# MAGI_sBatteryPower.net
KiCad netlist of a schematic drawn in Altium Designer
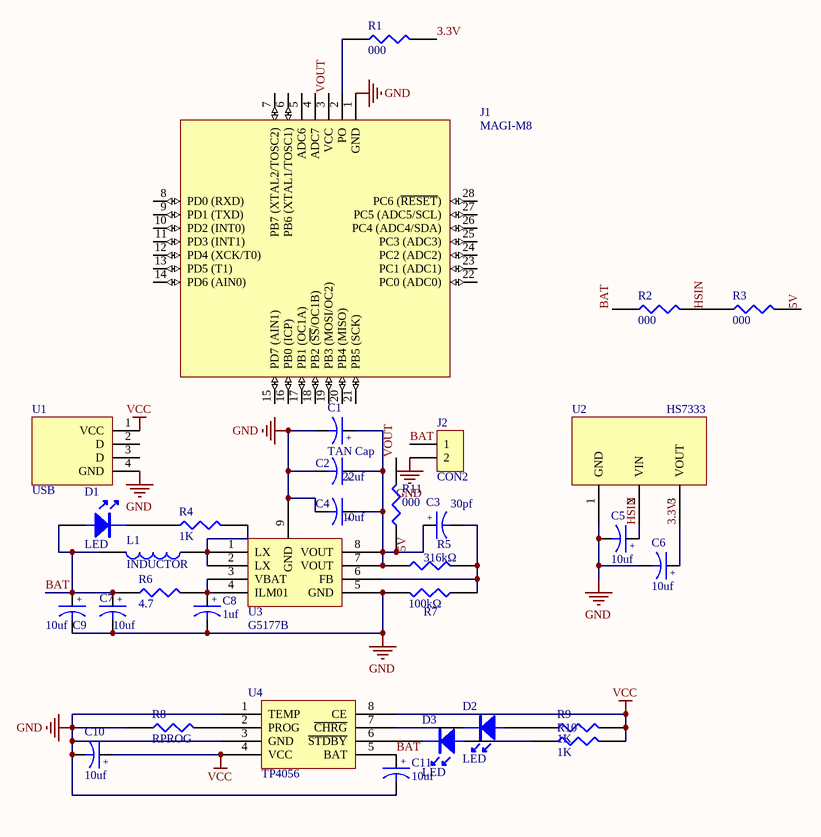
[diagram p0: MAGI'sBatteryPower.SchDoc]

(export (version "E")
  (design (tool "Eeschema 10.0.6"))
  (components
    (comp (ref "C1")
      (value "TAN Cap")
      (footprint "TAN-D-7343")
      (description "Capacitor")
      (libsource (lib "电容器") (part "CAPACITOR POL"))
    )
    (comp (ref "C2")
      (value "22uf")
      (footprint "14-1210")
      (description "Capacitor")
      (libsource (lib "电容器") (part "CAPACITOR POL"))
    )
    (comp (ref "C3")
      (value "30pf")
      (footprint "6-0805_N")
      (description "Capacitor")
      (libsource (lib "电容器") (part "CAPACITOR POL"))
    )
    (comp (ref "C4")
      (value "10uf")
      (footprint "6-0805_N")
      (description "Capacitor")
      (libsource (lib "电容器") (part "CAPACITOR POL"))
    )
    (comp (ref "C5")
      (value "10uf")
      (footprint "6-0805_N")
      (description "Capacitor")
      (libsource (lib "电容器") (part "CAPACITOR POL"))
    )
    (comp (ref "C6")
      (value "10uf")
      (footprint "6-0805_N")
      (description "Capacitor")
      (libsource (lib "电容器") (part "CAPACITOR POL"))
    )
    (comp (ref "C7")
      (value "10uf")
      (footprint "6-0805_N")
      (description "Capacitor")
      (libsource (lib "电容器") (part "CAPACITOR POL"))
    )
    (comp (ref "C8")
      (value "1uf")
      (footprint "6-0805_N")
      (description "Capacitor")
      (libsource (lib "电容器") (part "CAPACITOR POL"))
    )
    (comp (ref "C9")
      (value "10uf")
      (footprint "6-0805_N")
      (description "Capacitor")
      (libsource (lib "电容器") (part "CAPACITOR POL"))
    )
    (comp (ref "C10")
      (value "10uf")
      (footprint "6-0805_N")
      (description "Capacitor")
      (libsource (lib "电容器") (part "CAPACITOR POL"))
    )
    (comp (ref "C11")
      (value "10uf")
      (footprint "6-0805_N")
      (description "Capacitor")
      (libsource (lib "电容器") (part "CAPACITOR POL"))
    )
    (comp (ref "D1") (value "LED") (footprint "6-0805_N") (libsource (lib "二极管") (part "LED")))
    (comp (ref "D2") (value "LED") (footprint "6-0805_N") (libsource (lib "二极管") (part "LED")))
    (comp (ref "D3") (value "LED") (footprint "6-0805_N") (libsource (lib "二极管") (part "LED")))
    (comp (ref "J1") (value "MAGI-M8") (footprint "MAGI-M8") (libsource (lib "MAGI-M8") (part "MAGI-M8")))
    (comp (ref "J2")
      (value "CON2")
      (footprint "CON2")
      (description "Connector")
      (libsource (lib "CON系列") (part "CON2"))
    )
    (comp (ref "L1") (value "INDUCTOR") (footprint "7*7") (libsource (lib "汇总") (part "INDUCTOR")))
    (comp (ref "R1") (value "000") (footprint "6-0805_n") (libsource (lib "电阻器") (part "RES1")))
    (comp (ref "R2") (value "000") (footprint "1608[0603]") (libsource (lib "电阻器") (part "RES1")))
    (comp (ref "R3") (value "000") (footprint "1608[0603]") (libsource (lib "电阻器") (part "RES1")))
    (comp (ref "R4") (value "1K") (footprint "6-0805_N") (libsource (lib "电阻器") (part "RES1")))
    (comp (ref "R5") (value "316kΩ") (footprint "6-0805_N") (libsource (lib "电阻器") (part "RES1")))
    (comp (ref "R6") (value "4.7") (footprint "6-0805_N") (libsource (lib "电阻器") (part "RES1")))
    (comp (ref "R7") (value "100kΩ") (footprint "6-0805_N") (libsource (lib "电阻器") (part "RES1")))
    (comp (ref "R8") (value "RPROG") (footprint "6-0805_N") (libsource (lib "电阻器") (part "RES1")))
    (comp (ref "R9") (value "1K") (footprint "6-0805_N") (libsource (lib "电阻器") (part "RES1")))
    (comp (ref "R10") (value "1K") (footprint "6-0805_N") (libsource (lib "电阻器") (part "RES1")))
    (comp (ref "R11") (value "000") (footprint "6-0805_N") (libsource (lib "电阻器") (part "RES1")))
    (comp (ref "U1") (value "USB") (footprint "MicroUSB") (libsource (lib "USB接口") (part "USB")))
    (comp (ref "U2") (value "HS7333") (footprint "HS7333") (libsource (lib "PMIC") (part "HS7333")))
    (comp (ref "U3") (value "G5177B") (footprint "G5177B") (libsource (lib "PMIC") (part "G5177B")))
    (comp (ref "U4") (value "TP4056") (footprint "TP4056") (libsource (lib "PMIC") (part "TP4056")))
  )
  (nets
    (net (code "1") (name "/3.3V") (class "Default")
      (node (ref "C6") (pin "1") (pinfunction "1_1") (pintype "passive"))
      (node (ref "R1") (pin "2") (pinfunction "2_2") (pintype "passive"))
      (node (ref "U2") (pin "3") (pinfunction "VOUT_3") (pintype "passive"))
    )
    (net (code "2") (name "/5V") (class "Default")
      (node (ref "C1") (pin "1") (pinfunction "1_1") (pintype "passive"))
      (node (ref "C2") (pin "1") (pinfunction "1_1") (pintype "passive"))
      (node (ref "C3") (pin "1") (pinfunction "1_1") (pintype "passive"))
      (node (ref "C4") (pin "1") (pinfunction "1_1") (pintype "passive"))
      (node (ref "R11") (pin "1") (pinfunction "1_1") (pintype "passive"))
      (node (ref "R3") (pin "2") (pinfunction "2_2") (pintype "passive"))
      (node (ref "R5") (pin "1") (pinfunction "1_1") (pintype "passive"))
      (node (ref "U3") (pin "7") (pinfunction "VOUT_7") (pintype "passive"))
      (node (ref "U3") (pin "8") (pinfunction "VOUT_8") (pintype "passive"))
    )
    (net (code "3") (name "/BAT") (class "Default")
      (node (ref "C11") (pin "1") (pinfunction "1_1") (pintype "passive"))
      (node (ref "C7") (pin "1") (pinfunction "1_1") (pintype "passive"))
      (node (ref "C9") (pin "1") (pinfunction "1_1") (pintype "passive"))
      (node (ref "D1") (pin "1") (pinfunction "1_1") (pintype "passive"))
      (node (ref "J2") (pin "1") (pinfunction "1_1") (pintype "passive"))
      (node (ref "L1") (pin "2") (pinfunction "2_2") (pintype "passive"))
      (node (ref "R2") (pin "1") (pinfunction "1_1") (pintype "passive"))
      (node (ref "R6") (pin "1") (pinfunction "1_1") (pintype "passive"))
      (node (ref "U4") (pin "5") (pinfunction "BAT_5") (pintype "passive"))
    )
    (net (code "4") (name "/HSIN") (class "Default")
      (node (ref "C5") (pin "1") (pinfunction "1_1") (pintype "passive"))
      (node (ref "R2") (pin "2") (pinfunction "2_2") (pintype "passive"))
      (node (ref "R3") (pin "1") (pinfunction "1_1") (pintype "passive"))
      (node (ref "U2") (pin "2") (pinfunction "VIN_2") (pintype "passive"))
    )
    (net (code "5") (name "/VOUT") (class "Default")
      (node (ref "J1") (pin "3") (pinfunction "VCC_3") (pintype "power_in"))
      (node (ref "R11") (pin "2") (pinfunction "2_2") (pintype "passive"))
    )
    (net (code "6") (name "GND") (class "Default")
      (node (ref "C1") (pin "2") (pinfunction "2_2") (pintype "passive"))
      (node (ref "C10") (pin "2") (pinfunction "2_2") (pintype "passive"))
      (node (ref "C11") (pin "2") (pinfunction "2_2") (pintype "passive"))
      (node (ref "C2") (pin "2") (pinfunction "2_2") (pintype "passive"))
      (node (ref "C4") (pin "2") (pinfunction "2_2") (pintype "passive"))
      (node (ref "C5") (pin "2") (pinfunction "2_2") (pintype "passive"))
      (node (ref "C6") (pin "2") (pinfunction "2_2") (pintype "passive"))
      (node (ref "C7") (pin "2") (pinfunction "2_2") (pintype "passive"))
      (node (ref "C8") (pin "2") (pinfunction "2_2") (pintype "passive"))
      (node (ref "C9") (pin "2") (pinfunction "2_2") (pintype "passive"))
      (node (ref "J1") (pin "1") (pinfunction "GND_1") (pintype "power_in"))
      (node (ref "J2") (pin "2") (pinfunction "2_2") (pintype "passive"))
      (node (ref "R7") (pin "2") (pinfunction "2_2") (pintype "passive"))
      (node (ref "R8") (pin "1") (pinfunction "1_1") (pintype "passive"))
      (node (ref "U1") (pin "4") (pinfunction "GND_4") (pintype "passive"))
      (node (ref "U2") (pin "1") (pinfunction "GND_1") (pintype "passive"))
      (node (ref "U3") (pin "5") (pinfunction "GND_5") (pintype "passive"))
      (node (ref "U3") (pin "9") (pinfunction "GND_9") (pintype "passive"))
      (node (ref "U4") (pin "1") (pinfunction "TEMP_1") (pintype "passive"))
      (node (ref "U4") (pin "3") (pinfunction "GND_3") (pintype "passive"))
    )
    (net (code "7") (name "Net-(D1-Pad2)") (class "Default")
      (node (ref "D1") (pin "2") (pinfunction "2_2") (pintype "passive"))
      (node (ref "R4") (pin "1") (pinfunction "1_1") (pintype "passive"))
    )
    (net (code "8") (name "Net-(D2-Pad1)") (class "Default")
      (node (ref "D2") (pin "1") (pinfunction "1_1") (pintype "passive"))
      (node (ref "R9") (pin "1") (pinfunction "1_1") (pintype "passive"))
    )
    (net (code "9") (name "Net-(D3-Pad1)") (class "Default")
      (node (ref "D3") (pin "1") (pinfunction "1_1") (pintype "passive"))
      (node (ref "R10") (pin "1") (pinfunction "1_1") (pintype "passive"))
    )
    (net (code "10") (name "Net-(J1-PO)") (class "Default")
      (node (ref "J1") (pin "2") (pinfunction "PO_2") (pintype "power_in"))
      (node (ref "R1") (pin "1") (pinfunction "1_1") (pintype "passive"))
    )
    (net (code "11") (name "Net-(L1-Pad1)") (class "Default")
      (node (ref "L1") (pin "1") (pinfunction "1_1") (pintype "passive"))
      (node (ref "R4") (pin "2") (pinfunction "2_2") (pintype "passive"))
      (node (ref "U3") (pin "1") (pinfunction "LX_1") (pintype "passive"))
      (node (ref "U3") (pin "2") (pinfunction "LX_2") (pintype "passive"))
    )
    (net (code "12") (name "Net-(U3-FB)") (class "Default")
      (node (ref "C3") (pin "2") (pinfunction "2_2") (pintype "passive"))
      (node (ref "R5") (pin "2") (pinfunction "2_2") (pintype "passive"))
      (node (ref "R7") (pin "1") (pinfunction "1_1") (pintype "passive"))
      (node (ref "U3") (pin "6") (pinfunction "FB_6") (pintype "passive"))
    )
    (net (code "13") (name "Net-(U3-ILM01)") (class "Default")
      (node (ref "C8") (pin "1") (pinfunction "1_1") (pintype "passive"))
      (node (ref "R6") (pin "2") (pinfunction "2_2") (pintype "passive"))
      (node (ref "U3") (pin "3") (pinfunction "VBAT_3") (pintype "passive"))
      (node (ref "U3") (pin "4") (pinfunction "ILM01_4") (pintype "passive"))
    )
    (net (code "14") (name "Net-(U4-PROG)") (class "Default")
      (node (ref "R8") (pin "2") (pinfunction "2_2") (pintype "passive"))
      (node (ref "U4") (pin "2") (pinfunction "PROG_2") (pintype "passive"))
    )
    (net (code "15") (name "Net-(U4-~{CHRG})") (class "Default")
      (node (ref "D2") (pin "2") (pinfunction "2_2") (pintype "passive"))
      (node (ref "U4") (pin "7") (pinfunction "~{CHRG}_7") (pintype "passive"))
    )
    (net (code "16") (name "Net-(U4-~{STDBY})") (class "Default")
      (node (ref "D3") (pin "2") (pinfunction "2_2") (pintype "passive"))
      (node (ref "U4") (pin "6") (pinfunction "~{STDBY}_6") (pintype "passive"))
    )
    (net (code "17") (name "VCC") (class "Default")
      (node (ref "C10") (pin "1") (pinfunction "1_1") (pintype "passive"))
      (node (ref "R10") (pin "2") (pinfunction "2_2") (pintype "passive"))
      (node (ref "R9") (pin "2") (pinfunction "2_2") (pintype "passive"))
      (node (ref "U1") (pin "1") (pinfunction "VCC_1") (pintype "passive"))
      (node (ref "U4") (pin "4") (pinfunction "VCC_4") (pintype "passive"))
      (node (ref "U4") (pin "8") (pinfunction "CE_8") (pintype "passive"))
    )
    (net (code "18") (name "unconnected-(J1-ADC6-Pad5)") (class "Default")
      (node (ref "J1") (pin "5") (pinfunction "ADC6_5") (pintype "passive"))
    )
    (net (code "19") (name "unconnected-(J1-ADC7-Pad4)") (class "Default")
      (node (ref "J1") (pin "4") (pinfunction "ADC7_4") (pintype "passive"))
    )
    (net (code "20") (name "unconnected-(J1-PB0_(ICP)-Pad16)") (class "Default")
      (node (ref "J1") (pin "16") (pinfunction "PB0_(ICP)_16") (pintype "bidirectional"))
    )
    (net (code "21") (name "unconnected-(J1-PB1_(OC1A)-Pad17)") (class "Default")
      (node (ref "J1") (pin "17") (pinfunction "PB1_(OC1A)_17") (pintype "bidirectional"))
    )
    (net (code "22") (name "unconnected-(J1-PB2_(~{SS}{slash}OC1B)-Pad18)") (class "Default")
      (node (ref "J1") (pin "18") (pinfunction "PB2_(~{SS}/OC1B)_18") (pintype "bidirectional"))
    )
    (net (code "23") (name "unconnected-(J1-PB3_(MOSI{slash}OC2)-Pad19)") (class "Default")
      (node (ref "J1") (pin "19") (pinfunction "PB3_(MOSI/OC2)_19") (pintype "bidirectional"))
    )
    (net (code "24") (name "unconnected-(J1-PB4_(MISO)-Pad20)") (class "Default")
      (node (ref "J1") (pin "20") (pinfunction "PB4_(MISO)_20") (pintype "bidirectional"))
    )
    (net (code "25") (name "unconnected-(J1-PB5_(SCK)-Pad21)") (class "Default")
      (node (ref "J1") (pin "21") (pinfunction "PB5_(SCK)_21") (pintype "bidirectional"))
    )
    (net (code "26") (name "unconnected-(J1-PB6_(XTAL1{slash}TOSC1)-Pad6)") (class "Default")
      (node (ref "J1") (pin "6") (pinfunction "PB6_(XTAL1/TOSC1)_6") (pintype "bidirectional"))
    )
    (net (code "27") (name "unconnected-(J1-PB7_(XTAL2{slash}TOSC2)-Pad7)") (class "Default")
      (node (ref "J1") (pin "7") (pinfunction "PB7_(XTAL2/TOSC2)_7") (pintype "bidirectional"))
    )
    (net (code "28") (name "unconnected-(J1-PC0_(ADC0)-Pad22)") (class "Default")
      (node (ref "J1") (pin "22") (pinfunction "PC0_(ADC0)_22") (pintype "bidirectional"))
    )
    (net (code "29") (name "unconnected-(J1-PC1_(ADC1)-Pad23)") (class "Default")
      (node (ref "J1") (pin "23") (pinfunction "PC1_(ADC1)_23") (pintype "bidirectional"))
    )
    (net (code "30") (name "unconnected-(J1-PC2_(ADC2)-Pad24)") (class "Default")
      (node (ref "J1") (pin "24") (pinfunction "PC2_(ADC2)_24") (pintype "bidirectional"))
    )
    (net (code "31") (name "unconnected-(J1-PC3_(ADC3)-Pad25)") (class "Default")
      (node (ref "J1") (pin "25") (pinfunction "PC3_(ADC3)_25") (pintype "bidirectional"))
    )
    (net (code "32") (name "unconnected-(J1-PC4_(ADC4{slash}SDA)-Pad26)") (class "Default")
      (node (ref "J1") (pin "26") (pinfunction "PC4_(ADC4/SDA)_26") (pintype "bidirectional"))
    )
    (net (code "33") (name "unconnected-(J1-PC5_(ADC5{slash}SCL)-Pad27)") (class "Default")
      (node (ref "J1") (pin "27") (pinfunction "PC5_(ADC5/SCL)_27") (pintype "bidirectional"))
    )
    (net (code "34") (name "unconnected-(J1-PC6_(~{RESET})-Pad28)") (class "Default")
      (node (ref "J1") (pin "28") (pinfunction "PC6_(~{RESET})_28") (pintype "bidirectional"))
    )
    (net (code "35") (name "unconnected-(J1-PD0_(RXD)-Pad8)") (class "Default")
      (node (ref "J1") (pin "8") (pinfunction "PD0_(RXD)_8") (pintype "bidirectional"))
    )
    (net (code "36") (name "unconnected-(J1-PD1_(TXD)-Pad9)") (class "Default")
      (node (ref "J1") (pin "9") (pinfunction "PD1_(TXD)_9") (pintype "bidirectional"))
    )
    (net (code "37") (name "unconnected-(J1-PD2_(INT0)-Pad10)") (class "Default")
      (node (ref "J1") (pin "10") (pinfunction "PD2_(INT0)_10") (pintype "bidirectional"))
    )
    (net (code "38") (name "unconnected-(J1-PD3_(INT1)-Pad11)") (class "Default")
      (node (ref "J1") (pin "11") (pinfunction "PD3_(INT1)_11") (pintype "bidirectional"))
    )
    (net (code "39") (name "unconnected-(J1-PD4_(XCK{slash}T0)-Pad12)") (class "Default")
      (node (ref "J1") (pin "12") (pinfunction "PD4_(XCK/T0)_12") (pintype "bidirectional"))
    )
    (net (code "40") (name "unconnected-(J1-PD5_(T1)-Pad13)") (class "Default")
      (node (ref "J1") (pin "13") (pinfunction "PD5_(T1)_13") (pintype "bidirectional"))
    )
    (net (code "41") (name "unconnected-(J1-PD6_(AIN0)-Pad14)") (class "Default")
      (node (ref "J1") (pin "14") (pinfunction "PD6_(AIN0)_14") (pintype "bidirectional"))
    )
    (net (code "42") (name "unconnected-(J1-PD7_(AIN1)-Pad15)") (class "Default")
      (node (ref "J1") (pin "15") (pinfunction "PD7_(AIN1)_15") (pintype "bidirectional"))
    )
    (net (code "43") (name "unconnected-(U1-D-Pad2)") (class "Default")
      (node (ref "U1") (pin "2") (pinfunction "D_2") (pintype "passive"))
    )
    (net (code "44") (name "unconnected-(U1-D-Pad3)") (class "Default")
      (node (ref "U1") (pin "3") (pinfunction "D_3") (pintype "passive"))
    )
  )
)
